# audio.net
KiCad netlist of a schematic drawn in Altium Designer
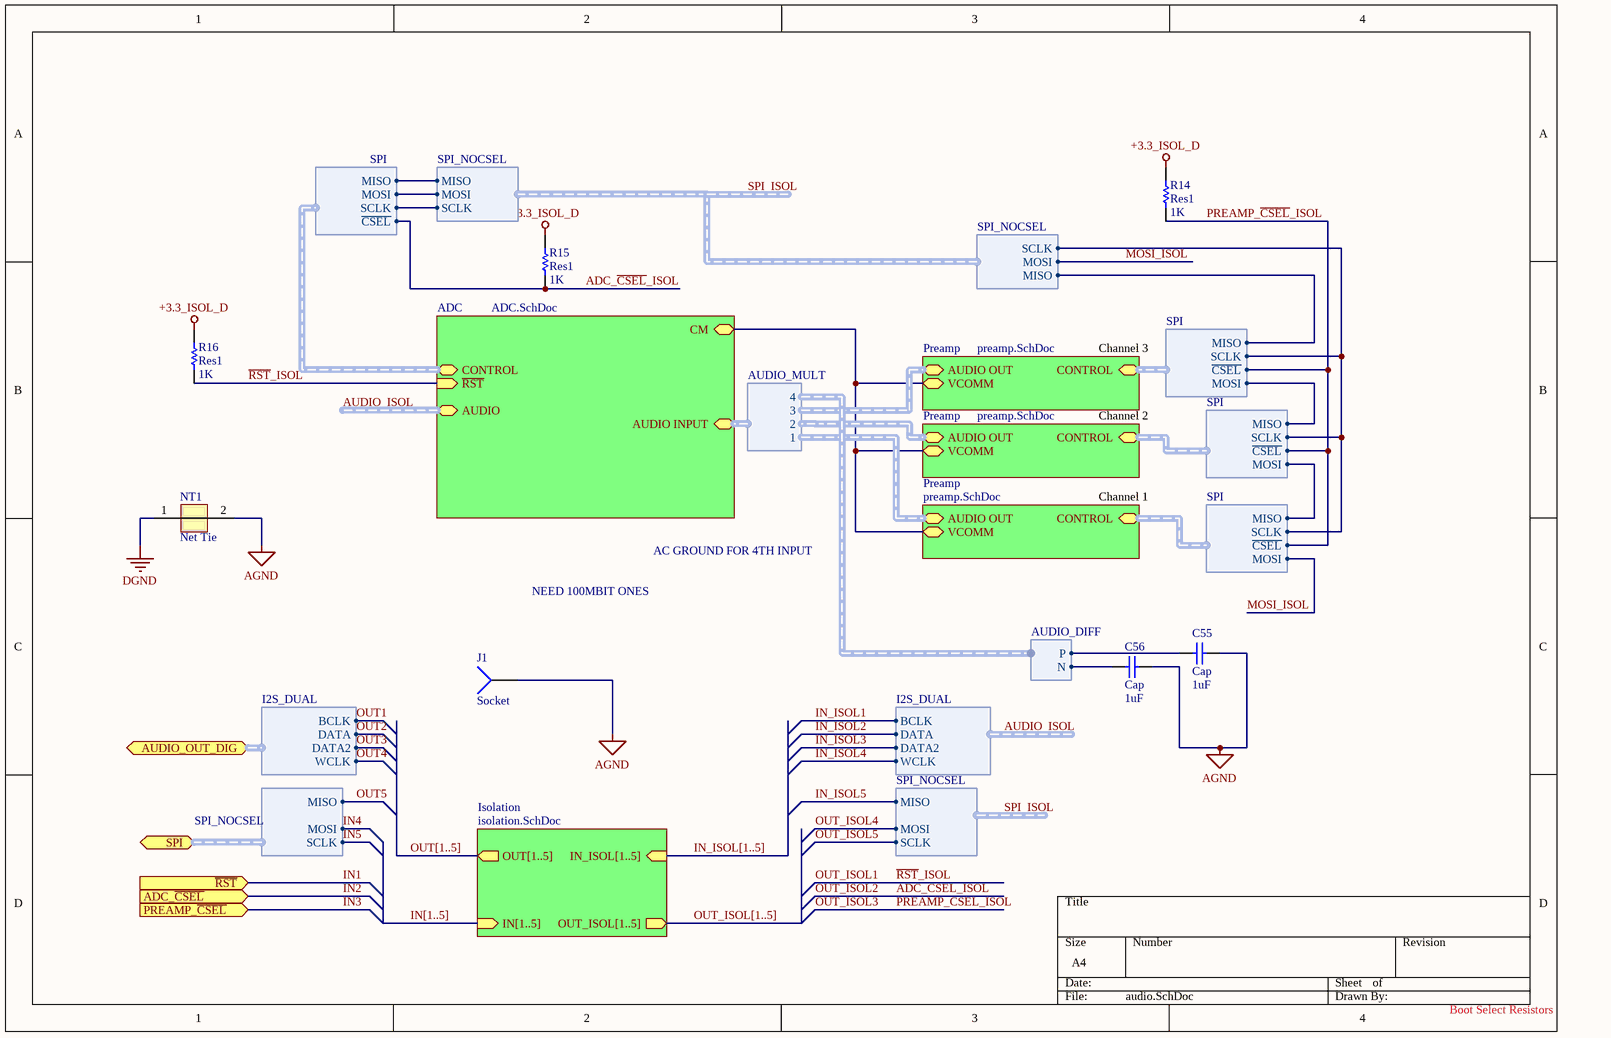
[diagram p0: audio.SchDoc]

(export (version "E")
  (design (tool "Eeschema 10.0.6"))
  (components
    (comp (ref "C55")
      (value "Cap")
      (footprint "C0603")
      (description "Capacitor")
      (fields (field (name "ALTIUM_VALUE") "1uF") (field (name "PUBLISHER") "Altium Limited"))
      (libsource (lib "Miscellaneous Devices") (part "Cap"))
    )
    (comp (ref "C56")
      (value "Cap")
      (footprint "C0603")
      (description "Capacitor")
      (fields (field (name "ALTIUM_VALUE") "1uF") (field (name "PUBLISHER") "Altium Limited"))
      (libsource (lib "Miscellaneous Devices") (part "Cap"))
    )
    (comp (ref "J1")
      (value "Socket")
      (footprint "PIN1")
      (fields (field (name "PUBLISHER") "Altium Limited"))
      (libsource (lib "Miscellaneous Connectors") (part "Socket"))
    )
    (comp (ref "NT1") (value "Net Tie") (footprint "NetTie") (libsource (lib "NetTie") (part "NetTie")))
    (comp (ref "R14")
      (value "Res1")
      (footprint "R0603")
      (description "Resistor")
      (fields (field (name "ALTIUM_VALUE") "1K") (field (name "PUBLISHER") "Altium Limited"))
      (libsource (lib "Miscellaneous Devices") (part "Res1"))
    )
    (comp (ref "R15")
      (value "Res1")
      (footprint "R0603")
      (description "Resistor")
      (fields (field (name "ALTIUM_VALUE") "1K") (field (name "PUBLISHER") "Altium Limited"))
      (libsource (lib "Miscellaneous Devices") (part "Res1"))
    )
    (comp (ref "R16")
      (value "Res1")
      (footprint "R0603")
      (description "Resistor")
      (fields (field (name "ALTIUM_VALUE") "1K") (field (name "PUBLISHER") "Altium Limited"))
      (libsource (lib "Miscellaneous Devices") (part "Res1"))
    )
  )
  (nets
    (net (code "9") (name "+3.3_ISOL_D") (class "Default")
      (node (ref "R14") (pin "2") (pinfunction "2_2") (pintype "passive"))
      (node (ref "R15") (pin "2") (pinfunction "2_2") (pintype "passive"))
      (node (ref "R16") (pin "2") (pinfunction "2_2") (pintype "passive"))
    )
    (net (code "27") (name "/N") (class "Default")
      (node (ref "C56") (pin "2") (pinfunction "2_2") (pintype "passive"))
    )
    (net (code "34") (name "/OUT_ISOL1") (class "Default")
      (node (ref "R16") (pin "1") (pinfunction "1_1") (pintype "passive"))
    )
    (net (code "35") (name "/OUT_ISOL2") (class "Default")
      (node (ref "R15") (pin "1") (pinfunction "1_1") (pintype "passive"))
    )
    (net (code "36") (name "/OUT_ISOL3") (class "Default")
      (node (ref "R14") (pin "1") (pinfunction "1_1") (pintype "passive"))
    )
    (net (code "40") (name "/P") (class "Default")
      (node (ref "C55") (pin "2") (pinfunction "2_2") (pintype "passive"))
    )
    (net (code "49") (name "AGND") (class "Default")
      (node (ref "C55") (pin "1") (pinfunction "1_1") (pintype "passive"))
      (node (ref "C56") (pin "1") (pinfunction "1_1") (pintype "passive"))
      (node (ref "J1") (pin "1") (pinfunction "1_1") (pintype "passive"))
      (node (ref "NT1") (pin "2") (pintype "passive"))
    )
    (net (code "50") (name "DGND") (class "Default") (node (ref "NT1") (pin "1") (pintype "passive")))
  )
)
